# 17_SPRINKL.net
KiCad netlist of a schematic drawn in EAGLE
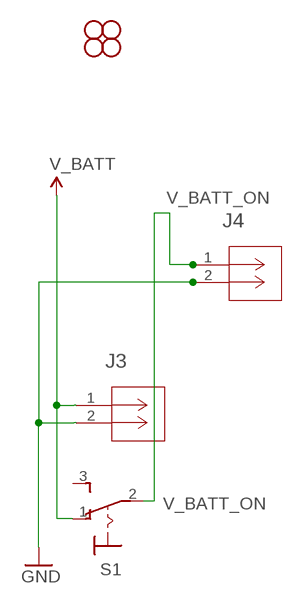
[diagram p0: schematic, sheet 1]
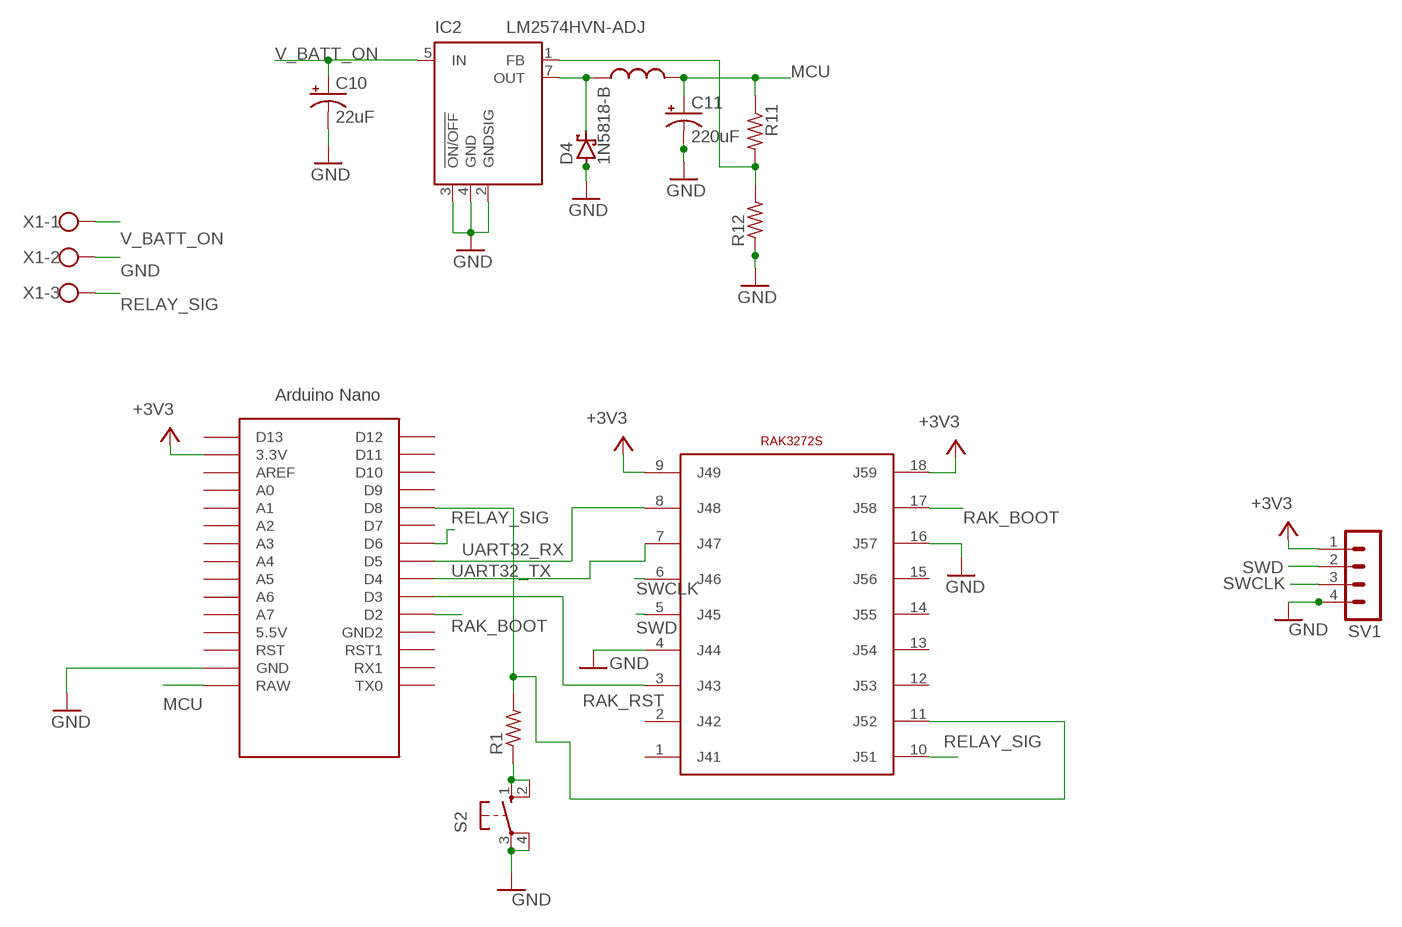
[diagram p1: schematic, sheet 2]

(export (version "E")
  (design (tool "Eeschema 10.0.6"))
  (components
    (comp (ref "J3")
      (value "1729128")
      (footprint "eagle-import:CONN_1729128_PXC")
      (fields (field (name "COPYRIGHT") "Copyright (C) 2023 Ultra Librarian. All rights reserved."))
      (libsource (lib "eagle-import") (part "1729128"))
    )
    (comp (ref "J4")
      (value "1729128")
      (footprint "eagle-import:CONN_1729128_PXC")
      (fields (field (name "COPYRIGHT") "Copyright (C) 2023 Ultra Librarian. All rights reserved."))
      (libsource (lib "eagle-import") (part "1729128"))
    )
    (comp (ref "S1")
      (value "M9040P")
      (footprint "eagle-import:M9040P")
      (libsource (lib "eagle-import") (part "M9040P"))
    )
    (comp (ref "STANDOFF1")
      (value "STAND-OFF")
      (footprint "eagle-import:STAND-OFF")
      (libsource (lib "eagle-import") (part "STAND-OFF"))
    )
    (comp (ref "STANDOFF2")
      (value "STAND-OFF")
      (footprint "eagle-import:STAND-OFF")
      (libsource (lib "eagle-import") (part "STAND-OFF"))
    )
    (comp (ref "STANDOFF3")
      (value "STAND-OFF")
      (footprint "eagle-import:STAND-OFF")
      (libsource (lib "eagle-import") (part "STAND-OFF"))
    )
    (comp (ref "STANDOFF4")
      (value "STAND-OFF")
      (footprint "eagle-import:STAND-OFF")
      (libsource (lib "eagle-import") (part "STAND-OFF"))
    )
    (comp (ref "C10")
      (value "22uF")
      (footprint "eagle-import:E5-6")
      (libsource (lib "eagle-import") (part "CPOL-USE5-6"))
    )
    (comp (ref "C11")
      (value "220uF")
      (footprint "eagle-import:E5-6")
      (libsource (lib "eagle-import") (part "CPOL-USE5-6"))
    )
    (comp (ref "D4")
      (value "1N5818-B")
      (footprint "eagle-import:DO41-7.6")
      (libsource (lib "eagle-import") (part "1N5818-B"))
    )
    (comp (ref "IC2")
      (value "LM2574HVN-ADJ")
      (footprint "eagle-import:DIL08")
      (libsource (lib "eagle-import") (part "LM2574?-HVNADJ"))
    )
    (comp (ref "R1")
      (value "R-US_0204/7")
      (footprint "eagle-import:0204_7")
      (libsource (lib "eagle-import") (part "R-US_0204/7"))
    )
    (comp (ref "R11")
      (value "R-US_0204/7")
      (footprint "eagle-import:0204_7")
      (libsource (lib "eagle-import") (part "R-US_0204/7"))
    )
    (comp (ref "R12")
      (value "R-US_0204/7")
      (footprint "eagle-import:0204_7")
      (libsource (lib "eagle-import") (part "R-US_0204/7"))
    )
    (comp (ref "S2")
      (value "10-XX")
      (footprint "eagle-import:B3F-10XX")
      (fields (field (name "MPN") "B3F-1000"))
      (libsource (lib "eagle-import") (part "10-XX"))
    )
    (comp (ref "SV1")
      (value "MA04-1")
      (footprint "eagle-import:MA04-1")
      (libsource (lib "eagle-import") (part "MA04-1"))
    )
    (comp (ref "U$1")
      (value "330UH_INDUCTOR")
      (footprint "eagle-import:330UH_INDUCTOR")
      (libsource (lib "eagle-import") (part "330UH_INDUCTOR"))
    )
    (comp (ref "U$3")
      (value "NANO")
      (footprint "eagle-import:NANO")
      (libsource (lib "eagle-import") (part "NANO"))
    )
    (comp (ref "U$4")
      (value "RAK3272S")
      (footprint "eagle-import:RAK3272SFOOTPRINT")
      (libsource (lib "eagle-import") (part "RAK3272S"))
    )
    (comp (ref "X1")
      (value "W237-103")
      (footprint "eagle-import:W237-103")
      (fields (field (name "MPN") "237-103"))
      (libsource (lib "eagle-import") (part "W237-103"))
    )
  )
  (nets
    (net (code "1") (name "+3V3") (class "Default")
      (node (ref "SV1") (pin "1") (pinfunction "1_1") (pintype "passive"))
      (node (ref "U$3") (pin "3.3V") (pinfunction "3.3V_3.3V") (pintype "bidirectional"))
      (node (ref "U$4") (pin "18") (pinfunction "J59_18") (pintype "bidirectional"))
      (node (ref "U$4") (pin "9") (pinfunction "J49_9") (pintype "bidirectional"))
    )
    (net (code "2") (name "GND") (class "Default")
      (node (ref "C10") (pin "-") (pinfunction "-_-") (pintype "passive"))
      (node (ref "C11") (pin "-") (pinfunction "-_-") (pintype "passive"))
      (node (ref "D4") (pin "A") (pinfunction "A_A") (pintype "passive"))
      (node (ref "IC2") (pin "2") (pinfunction "GNDSIG_2") (pintype "input"))
      (node (ref "IC2") (pin "3") (pinfunction "~{ON/OFF}_3") (pintype "input"))
      (node (ref "IC2") (pin "4") (pinfunction "GND_4") (pintype "power_in"))
      (node (ref "J3") (pin "2") (pinfunction "2_2") (pintype "passive"))
      (node (ref "J4") (pin "2") (pinfunction "2_2") (pintype "passive"))
      (node (ref "R12") (pin "1") (pinfunction "1_1") (pintype "passive"))
      (node (ref "S2") (pin "3") (pinfunction "P_3") (pintype "passive"))
      (node (ref "S2") (pin "4") (pinfunction "P1_4") (pintype "passive"))
      (node (ref "SV1") (pin "4") (pinfunction "4_4") (pintype "passive"))
      (node (ref "U$3") (pin "GND") (pinfunction "GND_GND") (pintype "bidirectional"))
      (node (ref "U$4") (pin "16") (pinfunction "J57_16") (pintype "bidirectional"))
      (node (ref "U$4") (pin "4") (pinfunction "J44_4") (pintype "bidirectional"))
      (node (ref "X1") (pin "2") (pinfunction "KL_2") (pintype "passive"))
    )
    (net (code "3") (name "MCU") (class "Default")
      (node (ref "C11") (pin "+") (pinfunction "+_+") (pintype "passive"))
      (node (ref "R11") (pin "1") (pinfunction "1_1") (pintype "passive"))
      (node (ref "U$1") (pin "P$2") (pinfunction "P$2_P$2") (pintype "bidirectional"))
      (node (ref "U$3") (pin "RAW") (pinfunction "RAW_RAW") (pintype "bidirectional"))
    )
    (net (code "4") (name "Net-(IC2-FB)") (class "Default")
      (node (ref "IC2") (pin "1") (pinfunction "FB_1") (pintype "input"))
      (node (ref "R11") (pin "2") (pinfunction "2_2") (pintype "passive"))
      (node (ref "R12") (pin "2") (pinfunction "2_2") (pintype "passive"))
    )
    (net (code "5") (name "Net-(IC2-OUT)") (class "Default")
      (node (ref "D4") (pin "C") (pinfunction "C_C") (pintype "passive"))
      (node (ref "IC2") (pin "7") (pinfunction "OUT_7") (pintype "passive"))
      (node (ref "U$1") (pin "P$1") (pinfunction "P$1_P$1") (pintype "bidirectional"))
    )
    (net (code "6") (name "Net-(S2-S)") (class "Default")
      (node (ref "R1") (pin "1") (pinfunction "1_1") (pintype "passive"))
      (node (ref "S2") (pin "1") (pinfunction "S_1") (pintype "passive"))
      (node (ref "S2") (pin "2") (pinfunction "S1_2") (pintype "passive"))
    )
    (net (code "7") (name "Net-(U$4-J52)") (class "Default")
      (node (ref "R1") (pin "2") (pinfunction "2_2") (pintype "passive"))
      (node (ref "U$3") (pin "D8") (pinfunction "D8_D8") (pintype "bidirectional"))
      (node (ref "U$4") (pin "11") (pinfunction "J52_11") (pintype "bidirectional"))
    )
    (net (code "8") (name "RAK_BOOT") (class "Default")
      (node (ref "U$3") (pin "D2") (pinfunction "D2_D2") (pintype "bidirectional"))
      (node (ref "U$4") (pin "17") (pinfunction "J58_17") (pintype "bidirectional"))
    )
    (net (code "9") (name "RAK_RST") (class "Default")
      (node (ref "U$3") (pin "D3") (pinfunction "D3_D3") (pintype "bidirectional"))
      (node (ref "U$4") (pin "3") (pinfunction "J43_3") (pintype "bidirectional"))
    )
    (net (code "10") (name "RELAY_SIG") (class "Default")
      (node (ref "U$3") (pin "D6") (pinfunction "D6_D6") (pintype "bidirectional"))
      (node (ref "U$4") (pin "10") (pinfunction "J51_10") (pintype "bidirectional"))
      (node (ref "X1") (pin "3") (pinfunction "KL_3") (pintype "passive"))
    )
    (net (code "11") (name "SWCLK") (class "Default")
      (node (ref "SV1") (pin "3") (pinfunction "3_3") (pintype "passive"))
      (node (ref "U$4") (pin "6") (pinfunction "J46_6") (pintype "bidirectional"))
    )
    (net (code "12") (name "SWD") (class "Default")
      (node (ref "SV1") (pin "2") (pinfunction "2_2") (pintype "passive"))
      (node (ref "U$4") (pin "5") (pinfunction "J45_5") (pintype "bidirectional"))
    )
    (net (code "13") (name "UART32_RX") (class "Default")
      (node (ref "U$3") (pin "D4") (pinfunction "D4_D4") (pintype "bidirectional"))
      (node (ref "U$4") (pin "7") (pinfunction "J47_7") (pintype "bidirectional"))
    )
    (net (code "14") (name "UART32_TX") (class "Default")
      (node (ref "U$3") (pin "D5") (pinfunction "D5_D5") (pintype "bidirectional"))
      (node (ref "U$4") (pin "8") (pinfunction "J48_8") (pintype "bidirectional"))
    )
    (net (code "15") (name "V_BATT") (class "Default")
      (node (ref "J3") (pin "1") (pinfunction "1_1") (pintype "passive"))
      (node (ref "S1") (pin "1") (pinfunction "O_1") (pintype "passive"))
    )
    (net (code "16") (name "V_BATT_ON") (class "Default")
      (node (ref "C10") (pin "+") (pinfunction "+_+") (pintype "passive"))
      (node (ref "IC2") (pin "5") (pinfunction "IN_5") (pintype "input"))
      (node (ref "J4") (pin "1") (pinfunction "1_1") (pintype "passive"))
      (node (ref "S1") (pin "2") (pinfunction "P_2") (pintype "passive"))
      (node (ref "X1") (pin "1") (pinfunction "KL_1") (pintype "passive"))
    )
    (net (code "17") (name "unconnected-(S1-S-Pad3)") (class "Default")
      (node (ref "S1") (pin "3") (pinfunction "S_3") (pintype "passive"))
    )
    (net (code "18") (name "unconnected-(U$3-5.5V-Pad5V)") (class "Default")
      (node (ref "U$3") (pin "5V") (pinfunction "5.5V_5V") (pintype "bidirectional"))
    )
    (net (code "19") (name "unconnected-(U$3-GND2-PadGND1)") (class "Default")
      (node (ref "U$3") (pin "GND1") (pinfunction "GND2_GND1") (pintype "bidirectional"))
    )
    (net (code "20") (name "unconnected-(U$3-PadA0)") (class "Default")
      (node (ref "U$3") (pin "A0") (pinfunction "A0_A0") (pintype "bidirectional"))
    )
    (net (code "21") (name "unconnected-(U$3-PadA1)") (class "Default")
      (node (ref "U$3") (pin "A1") (pinfunction "A1_A1") (pintype "bidirectional"))
    )
    (net (code "22") (name "unconnected-(U$3-PadA2)") (class "Default")
      (node (ref "U$3") (pin "A2") (pinfunction "A2_A2") (pintype "bidirectional"))
    )
    (net (code "23") (name "unconnected-(U$3-PadA3)") (class "Default")
      (node (ref "U$3") (pin "A3") (pinfunction "A3_A3") (pintype "bidirectional"))
    )
    (net (code "24") (name "unconnected-(U$3-PadA4)") (class "Default")
      (node (ref "U$3") (pin "A4") (pinfunction "A4_A4") (pintype "bidirectional"))
    )
    (net (code "25") (name "unconnected-(U$3-PadA5)") (class "Default")
      (node (ref "U$3") (pin "A5") (pinfunction "A5_A5") (pintype "bidirectional"))
    )
    (net (code "26") (name "unconnected-(U$3-PadA6)") (class "Default")
      (node (ref "U$3") (pin "A6") (pinfunction "A6_A6") (pintype "bidirectional"))
    )
    (net (code "27") (name "unconnected-(U$3-PadA7)") (class "Default")
      (node (ref "U$3") (pin "A7") (pinfunction "A7_A7") (pintype "bidirectional"))
    )
    (net (code "28") (name "unconnected-(U$3-PadAREF)") (class "Default")
      (node (ref "U$3") (pin "AREF") (pinfunction "AREF_AREF") (pintype "bidirectional"))
    )
    (net (code "29") (name "unconnected-(U$3-PadD7)") (class "Default")
      (node (ref "U$3") (pin "D7") (pinfunction "D7_D7") (pintype "bidirectional"))
    )
    (net (code "30") (name "unconnected-(U$3-PadD9)") (class "Default")
      (node (ref "U$3") (pin "D9") (pinfunction "D9_D9") (pintype "bidirectional"))
    )
    (net (code "31") (name "unconnected-(U$3-PadD10)") (class "Default")
      (node (ref "U$3") (pin "D10") (pinfunction "D10_D10") (pintype "bidirectional"))
    )
    (net (code "32") (name "unconnected-(U$3-PadD11)") (class "Default")
      (node (ref "U$3") (pin "D11") (pinfunction "D11_D11") (pintype "bidirectional"))
    )
    (net (code "33") (name "unconnected-(U$3-PadD12)") (class "Default")
      (node (ref "U$3") (pin "D12") (pinfunction "D12_D12") (pintype "bidirectional"))
    )
    (net (code "34") (name "unconnected-(U$3-PadD13)") (class "Default")
      (node (ref "U$3") (pin "D13") (pinfunction "D13_D13") (pintype "bidirectional"))
    )
    (net (code "35") (name "unconnected-(U$3-PadICSP1)") (class "Default")
      (node (ref "U$3") (pin "ICSP1") (pinfunction "ICSP1_ICSP1") (pintype "bidirectional"))
    )
    (net (code "36") (name "unconnected-(U$3-PadICSP2)") (class "Default")
      (node (ref "U$3") (pin "ICSP2") (pinfunction "ICSP2_ICSP2") (pintype "bidirectional"))
    )
    (net (code "37") (name "unconnected-(U$3-PadICSP3)") (class "Default")
      (node (ref "U$3") (pin "ICSP3") (pinfunction "ICSP3_ICSP3") (pintype "bidirectional"))
    )
    (net (code "38") (name "unconnected-(U$3-PadICSP4)") (class "Default")
      (node (ref "U$3") (pin "ICSP4") (pinfunction "ICSP4_ICSP4") (pintype "bidirectional"))
    )
    (net (code "39") (name "unconnected-(U$3-PadICSP5)") (class "Default")
      (node (ref "U$3") (pin "ICSP5") (pinfunction "ICSP5_ICSP5") (pintype "bidirectional"))
    )
    (net (code "40") (name "unconnected-(U$3-PadICSP6)") (class "Default")
      (node (ref "U$3") (pin "ICSP6") (pinfunction "ICSP6_ICSP6") (pintype "bidirectional"))
    )
    (net (code "41") (name "unconnected-(U$3-PadRST)") (class "Default")
      (node (ref "U$3") (pin "RST") (pinfunction "RST_RST") (pintype "bidirectional"))
    )
    (net (code "42") (name "unconnected-(U$3-PadRST1)") (class "Default")
      (node (ref "U$3") (pin "RST1") (pinfunction "RST1_RST1") (pintype "bidirectional"))
    )
    (net (code "43") (name "unconnected-(U$3-PadRX1)") (class "Default")
      (node (ref "U$3") (pin "RX1") (pinfunction "RX1_RX1") (pintype "bidirectional"))
    )
    (net (code "44") (name "unconnected-(U$3-PadTX0)") (class "Default")
      (node (ref "U$3") (pin "TX0") (pinfunction "TX0_TX0") (pintype "bidirectional"))
    )
    (net (code "45") (name "unconnected-(U$4-J41-Pad1)") (class "Default")
      (node (ref "U$4") (pin "1") (pinfunction "J41_1") (pintype "bidirectional"))
    )
    (net (code "46") (name "unconnected-(U$4-J42-Pad2)") (class "Default")
      (node (ref "U$4") (pin "2") (pinfunction "J42_2") (pintype "bidirectional"))
    )
    (net (code "47") (name "unconnected-(U$4-J53-Pad12)") (class "Default")
      (node (ref "U$4") (pin "12") (pinfunction "J53_12") (pintype "bidirectional"))
    )
    (net (code "48") (name "unconnected-(U$4-J54-Pad13)") (class "Default")
      (node (ref "U$4") (pin "13") (pinfunction "J54_13") (pintype "bidirectional"))
    )
    (net (code "49") (name "unconnected-(U$4-J55-Pad14)") (class "Default")
      (node (ref "U$4") (pin "14") (pinfunction "J55_14") (pintype "bidirectional"))
    )
    (net (code "50") (name "unconnected-(U$4-J56-Pad15)") (class "Default")
      (node (ref "U$4") (pin "15") (pinfunction "J56_15") (pintype "bidirectional"))
    )
  )
)
